# SAMARUC.net
KiCad netlist of a schematic drawn in Altium Designer
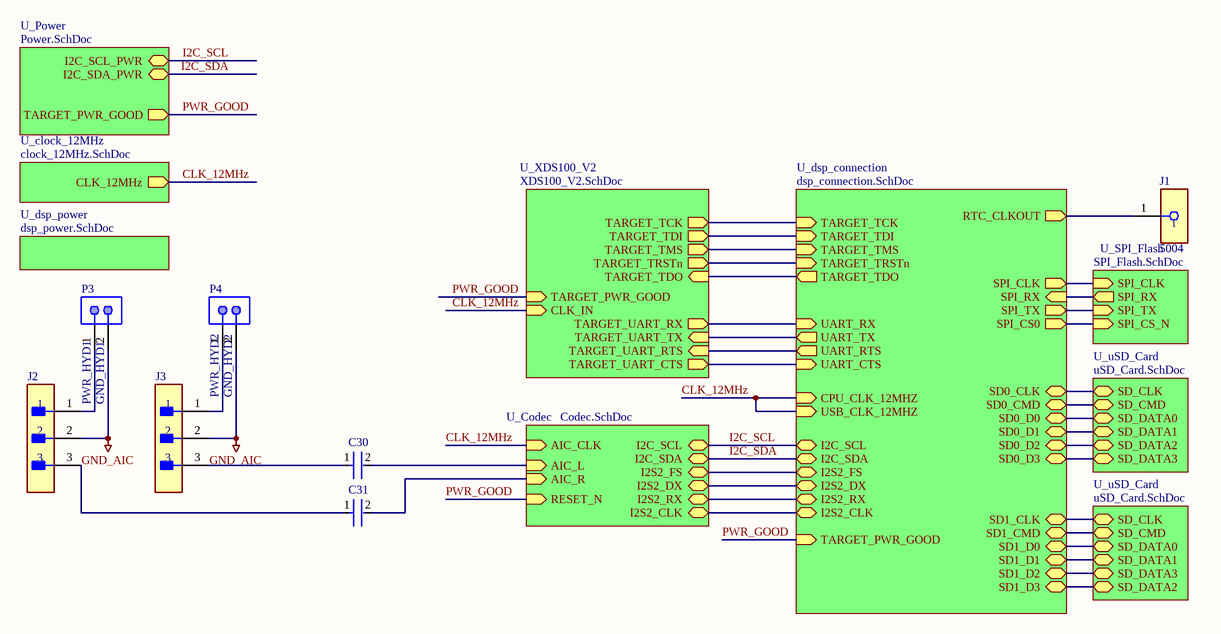
[diagram p0: SAMARUC.SchDoc]

(export (version "E")
  (design (tool "Eeschema 10.0.6"))
  (components
    (comp (ref "C30")
      (value "RCER71H106MWK1H03B")
      (footprint "FP-RCEWM1-MFG")
      (description "Cap Ceramic 10uF 50V X7R ±20% Radial 5mm +125°C Automotive Ammo Pack")
      (fields (field (name "TOLERANCE") "20%") (field (name "VOLTAGE") "50V"))
      (libsource (lib "Altium Content Vault") (part "02cd4be3c70576c341d710602a673aa"))
    )
    (comp (ref "C31")
      (value "RCER71H106MWK1H03B")
      (footprint "FP-RCEWM1-MFG")
      (description "Cap Ceramic 10uF 50V X7R ±20% Radial 5mm +125°C Automotive Ammo Pack")
      (fields (field (name "TOLERANCE") "20%") (field (name "VOLTAGE") "50V"))
      (libsource (lib "Altium Content Vault") (part "02cd4be3c70576c341d710602a673aa"))
    )
    (comp (ref "J1")
      (value "5004")
      (footprint "FP-5004-MFG")
      (description "PC TEST POINT MINIATURE YELLOW")
      (fields
        (field (name "MANUFACTURER") "Keystone")
        (field (name "OCTOPART") "https://octopart.com/5004-keystone-28591")
      )
      (libsource (lib "Altium Content Vault") (part "98815daf2f2c152b0c43f5ab9800df6"))
    )
    (comp (ref "J2")
      (value "22-11-2032")
      (footprint "FP-22-11-2032-MFG")
      (description "CONN HEADER VERT 3POS 2.54MM")
      (fields
        (field (name "MANUFACTURER") "Molex")
        (field (name "OCTOPART") "https://octopart.com/22-11-2032-molex-10085")
      )
      (libsource (lib "Altium Content Vault") (part "0d3f023dd272f625e17a2be33dea85f"))
    )
    (comp (ref "J3")
      (value "22-11-2032")
      (footprint "FP-22-11-2032-MFG")
      (description "CONN HEADER VERT 3POS 2.54MM")
      (fields
        (field (name "MANUFACTURER") "Molex")
        (field (name "OCTOPART") "https://octopart.com/22-11-2032-molex-10085")
      )
      (libsource (lib "Altium Content Vault") (part "0d3f023dd272f625e17a2be33dea85f"))
    )
    (comp (ref "P3")
      (value "22-23-2021")
      (footprint "MOLX-22-23-2021_V")
      (libsource (lib "Altium Content Vault") (part "CN-1P-M-R2"))
    )
    (comp (ref "P4")
      (value "22-23-2021")
      (footprint "MOLX-22-23-2021_V")
      (libsource (lib "Altium Content Vault") (part "CN-1P-M-R2"))
    )
  )
  (nets
    (net (code "1") (name "/AIC_L") (class "Default")
      (node (ref "C30") (pin "2") (pinfunction "2_2") (pintype "passive"))
    )
    (net (code "2") (name "/AIC_R") (class "Default")
      (node (ref "C31") (pin "2") (pinfunction "2_2") (pintype "passive"))
    )
    (net (code "11") (name "/RTC_CLKOUT") (class "Default")
      (node (ref "J1") (pin "1") (pinfunction "1_1") (pintype "passive"))
    )
    (net (code "37") (name "GND_AIC") (class "Default")
      (node (ref "J2") (pin "2") (pinfunction "2_2") (pintype "passive"))
      (node (ref "J3") (pin "2") (pinfunction "2_2") (pintype "passive"))
      (node (ref "P3") (pin "2") (pinfunction "2_2") (pintype "passive"))
      (node (ref "P4") (pin "2") (pinfunction "2_2") (pintype "passive"))
    )
    (net (code "38") (name "Net-(C30-Pad1)") (class "Default")
      (node (ref "C30") (pin "1") (pinfunction "1_1") (pintype "passive"))
      (node (ref "J3") (pin "3") (pinfunction "3_3") (pintype "passive"))
    )
    (net (code "39") (name "Net-(C31-Pad1)") (class "Default")
      (node (ref "C31") (pin "1") (pinfunction "1_1") (pintype "passive"))
      (node (ref "J2") (pin "3") (pinfunction "3_3") (pintype "passive"))
    )
    (net (code "40") (name "Net-(J2-Pad1)") (class "Default")
      (node (ref "J2") (pin "1") (pinfunction "1_1") (pintype "passive"))
      (node (ref "P3") (pin "1") (pinfunction "1_1") (pintype "passive"))
    )
    (net (code "41") (name "Net-(J3-Pad1)") (class "Default")
      (node (ref "J3") (pin "1") (pinfunction "1_1") (pintype "passive"))
      (node (ref "P4") (pin "1") (pinfunction "1_1") (pintype "passive"))
    )
  )
)
